# lpf6.net
KiCad netlist of a schematic drawn in Altium Designer
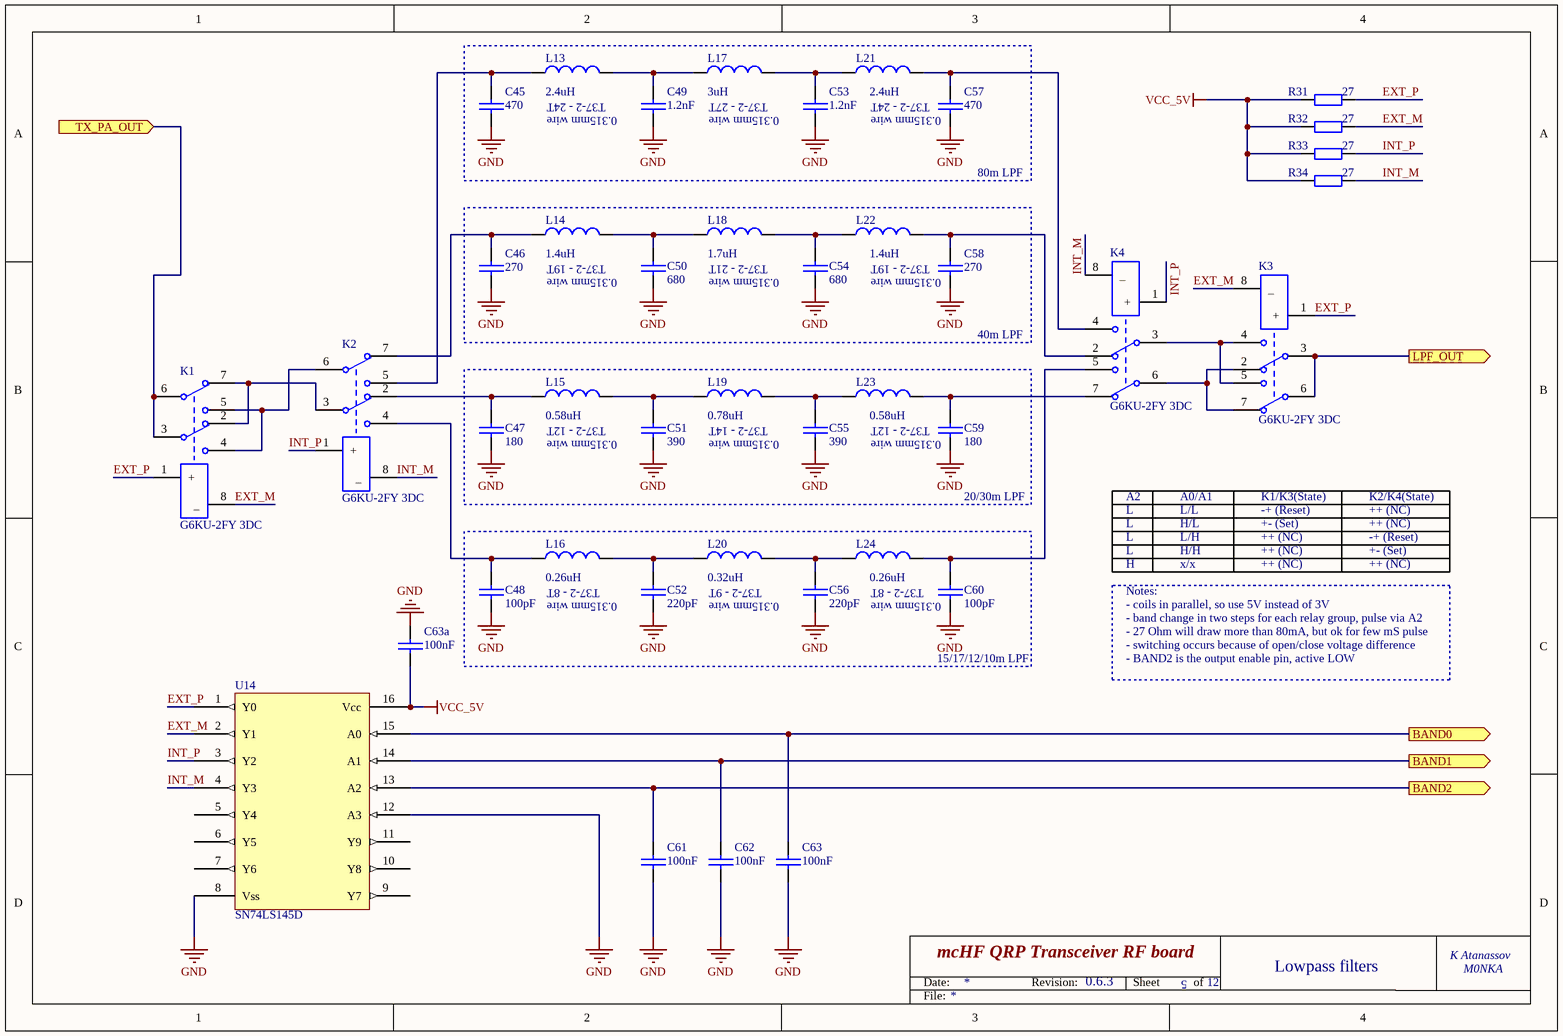
[diagram p0: lpf6.SchDoc]

(export (version "E")
  (design (tool "Eeschema 10.0.6"))
  (components
    (comp (ref "C45")
      (value "470")
      (footprint "0805-Pro")
      (description "Capacitor")
      (libsource (lib "mcHF_rf") (part "CAP"))
    )
    (comp (ref "C46")
      (value "270")
      (footprint "0805-Pro")
      (description "Capacitor")
      (libsource (lib "mcHF_rf") (part "CAP"))
    )
    (comp (ref "C47")
      (value "180")
      (footprint "0805-Pro")
      (description "Capacitor")
      (libsource (lib "mcHF_rf") (part "CAP"))
    )
    (comp (ref "C48")
      (value "100pF")
      (footprint "0805-Pro")
      (description "Capacitor")
      (libsource (lib "mcHF_rf") (part "CAP"))
    )
    (comp (ref "C49")
      (value "1.2nF")
      (footprint "0805-Pro")
      (description "Capacitor")
      (libsource (lib "mcHF_rf") (part "CAP"))
    )
    (comp (ref "C50")
      (value "680")
      (footprint "0805-Pro")
      (description "Capacitor")
      (libsource (lib "mcHF_rf") (part "CAP"))
    )
    (comp (ref "C51")
      (value "390")
      (footprint "0805-Pro")
      (description "Capacitor")
      (libsource (lib "mcHF_rf") (part "CAP"))
    )
    (comp (ref "C52")
      (value "220pF")
      (footprint "0805-Pro")
      (description "Capacitor")
      (libsource (lib "mcHF_rf") (part "CAP"))
    )
    (comp (ref "C53")
      (value "1.2nF")
      (footprint "0805-Pro")
      (description "Capacitor")
      (libsource (lib "mcHF_rf") (part "CAP"))
    )
    (comp (ref "C54")
      (value "680")
      (footprint "0805-Pro")
      (description "Capacitor")
      (libsource (lib "mcHF_rf") (part "CAP"))
    )
    (comp (ref "C55")
      (value "390")
      (footprint "0805-Pro")
      (description "Capacitor")
      (libsource (lib "mcHF_rf") (part "CAP"))
    )
    (comp (ref "C56")
      (value "220pF")
      (footprint "0805-Pro")
      (description "Capacitor")
      (libsource (lib "mcHF_rf") (part "CAP"))
    )
    (comp (ref "C57")
      (value "470")
      (footprint "0805-Pro")
      (description "Capacitor")
      (libsource (lib "mcHF_rf") (part "CAP"))
    )
    (comp (ref "C58")
      (value "270")
      (footprint "0805-Pro")
      (description "Capacitor")
      (libsource (lib "mcHF_rf") (part "CAP"))
    )
    (comp (ref "C59")
      (value "180")
      (footprint "0805-Pro")
      (description "Capacitor")
      (libsource (lib "mcHF_rf") (part "CAP"))
    )
    (comp (ref "C60")
      (value "100pF")
      (footprint "0805-Pro")
      (description "Capacitor")
      (libsource (lib "mcHF_rf") (part "CAP"))
    )
    (comp (ref "C61")
      (value "100nF")
      (footprint "0805-Pro")
      (description "Capacitor")
      (libsource (lib "mcHF_rf") (part "CAP"))
    )
    (comp (ref "C62")
      (value "100nF")
      (footprint "0805-Pro")
      (description "Capacitor")
      (libsource (lib "mcHF_rf") (part "CAP"))
    )
    (comp (ref "C63")
      (value "100nF")
      (footprint "0805-Pro")
      (description "Capacitor")
      (libsource (lib "mcHF_rf") (part "CAP"))
    )
    (comp (ref "C63a")
      (value "100nF")
      (footprint "0805-Pro")
      (description "Capacitor")
      (libsource (lib "mcHF_rf") (part "CAP"))
    )
    (comp (ref "K1")
      (value "G6KU-2FY 3DC")
      (footprint "Omron_2FY")
      (description "Single-winding Latching Relay")
      (libsource (lib "mcHF_rf") (part "G6KU-2FY 3DC"))
    )
    (comp (ref "K2")
      (value "G6KU-2FY 3DC")
      (footprint "Omron_2FY")
      (description "Single-winding Latching Relay")
      (libsource (lib "mcHF_rf") (part "G6KU-2FY 3DC"))
    )
    (comp (ref "K3")
      (value "G6KU-2FY 3DC")
      (footprint "Omron_2FY")
      (description "Single-winding Latching Relay")
      (libsource (lib "mcHF_rf") (part "G6KU-2FY 3DC"))
    )
    (comp (ref "K4")
      (value "G6KU-2FY 3DC")
      (footprint "Omron_2FY")
      (description "Single-winding Latching Relay")
      (libsource (lib "mcHF_rf") (part "G6KU-2FY 3DC"))
    )
    (comp (ref "L13")
      (value "T37-2")
      (footprint "LPF_IND")
      (description "T37-2 handwound inductor")
      (fields (field (name "INDUCTANCE") "2.4uH"))
      (libsource (lib "mcHF_rf") (part "LPF_IND"))
    )
    (comp (ref "L14")
      (value "T37-2")
      (footprint "LPF_IND")
      (description "T37-2 handwound inductor")
      (fields (field (name "INDUCTANCE") "1.4uH"))
      (libsource (lib "mcHF_rf") (part "LPF_IND"))
    )
    (comp (ref "L15")
      (value "T37-2")
      (footprint "LPF_IND")
      (description "T37-2 handwound inductor")
      (fields (field (name "INDUCTANCE") "0.58uH"))
      (libsource (lib "mcHF_rf") (part "LPF_IND"))
    )
    (comp (ref "L16")
      (value "T37-2")
      (footprint "LPF_IND")
      (description "T37-2 handwound inductor")
      (fields (field (name "INDUCTANCE") "0.26uH"))
      (libsource (lib "mcHF_rf") (part "LPF_IND"))
    )
    (comp (ref "L17")
      (value "T37-2")
      (footprint "LPF_IND")
      (description "T37-2 handwound inductor")
      (fields (field (name "INDUCTANCE") "3uH"))
      (libsource (lib "mcHF_rf") (part "LPF_IND"))
    )
    (comp (ref "L18")
      (value "T37-2")
      (footprint "LPF_IND")
      (description "T37-2 handwound inductor")
      (fields (field (name "INDUCTANCE") "1.7uH"))
      (libsource (lib "mcHF_rf") (part "LPF_IND"))
    )
    (comp (ref "L19")
      (value "T37-2")
      (footprint "LPF_IND")
      (description "T37-2 handwound inductor")
      (fields (field (name "INDUCTANCE") "0.78uH"))
      (libsource (lib "mcHF_rf") (part "LPF_IND"))
    )
    (comp (ref "L20")
      (value "T37-2")
      (footprint "LPF_IND")
      (description "T37-2 handwound inductor")
      (fields (field (name "INDUCTANCE") "0.32uH"))
      (libsource (lib "mcHF_rf") (part "LPF_IND"))
    )
    (comp (ref "L21")
      (value "T37-2")
      (footprint "LPF_IND")
      (description "T37-2 handwound inductor")
      (fields (field (name "INDUCTANCE") "2.4uH"))
      (libsource (lib "mcHF_rf") (part "LPF_IND"))
    )
    (comp (ref "L22")
      (value "T37-2")
      (footprint "LPF_IND")
      (description "T37-2 handwound inductor")
      (fields (field (name "INDUCTANCE") "1.4uH"))
      (libsource (lib "mcHF_rf") (part "LPF_IND"))
    )
    (comp (ref "L23")
      (value "T37-2")
      (footprint "LPF_IND")
      (description "T37-2 handwound inductor")
      (fields (field (name "INDUCTANCE") "0.58uH"))
      (libsource (lib "mcHF_rf") (part "LPF_IND"))
    )
    (comp (ref "L24")
      (value "T37-2")
      (footprint "LPF_IND")
      (description "T37-2 handwound inductor")
      (fields (field (name "INDUCTANCE") "0.26uH"))
      (libsource (lib "mcHF_rf") (part "LPF_IND"))
    )
    (comp (ref "R31")
      (value "27")
      (footprint "1206")
      (description "Resistor")
      (libsource (lib "mcHF_rf") (part "RES"))
    )
    (comp (ref "R32")
      (value "27")
      (footprint "1206")
      (description "Resistor")
      (libsource (lib "mcHF_rf") (part "RES"))
    )
    (comp (ref "R33")
      (value "27")
      (footprint "1206")
      (description "Resistor")
      (libsource (lib "mcHF_rf") (part "RES"))
    )
    (comp (ref "R34")
      (value "27")
      (footprint "1206")
      (description "Resistor")
      (libsource (lib "mcHF_rf") (part "RES"))
    )
    (comp (ref "U14")
      (value "SN74LS145D")
      (footprint "SO-16-Pro")
      (description "BCD DECODER/DRIVER")
      (libsource (lib "mcHF_rf") (part "SN74LS145D"))
    )
  )
  (nets
    (net (code "1") (name "/BAND0") (class "Default")
      (node (ref "C63") (pin "2") (pinfunction "2_2") (pintype "passive"))
      (node (ref "U14") (pin "15") (pinfunction "A0_15") (pintype "input"))
    )
    (net (code "2") (name "/BAND1") (class "Default")
      (node (ref "C62") (pin "2") (pinfunction "2_2") (pintype "passive"))
      (node (ref "U14") (pin "14") (pinfunction "A1_14") (pintype "input"))
    )
    (net (code "3") (name "/BAND2") (class "Default")
      (node (ref "C61") (pin "2") (pinfunction "2_2") (pintype "passive"))
      (node (ref "U14") (pin "13") (pinfunction "A2_13") (pintype "input"))
    )
    (net (code "4") (name "/EXT_M") (class "Default")
      (node (ref "K1") (pin "8") (pinfunction "__8") (pintype "passive"))
      (node (ref "K3") (pin "8") (pinfunction "__8") (pintype "passive"))
      (node (ref "R32") (pin "1") (pinfunction "1_1") (pintype "passive"))
      (node (ref "U14") (pin "2") (pinfunction "Y1_2") (pintype "output"))
    )
    (net (code "5") (name "/EXT_P") (class "Default")
      (node (ref "K1") (pin "1") (pinfunction "+_1") (pintype "passive"))
      (node (ref "K3") (pin "1") (pinfunction "+_1") (pintype "passive"))
      (node (ref "R31") (pin "1") (pinfunction "1_1") (pintype "passive"))
      (node (ref "U14") (pin "1") (pinfunction "Y0_1") (pintype "output"))
    )
    (net (code "6") (name "/INT_M") (class "Default")
      (node (ref "K2") (pin "8") (pinfunction "__8") (pintype "passive"))
      (node (ref "K4") (pin "8") (pinfunction "__8") (pintype "passive"))
      (node (ref "R34") (pin "1") (pinfunction "1_1") (pintype "passive"))
      (node (ref "U14") (pin "4") (pinfunction "Y3_4") (pintype "output"))
    )
    (net (code "7") (name "/INT_P") (class "Default")
      (node (ref "K2") (pin "1") (pinfunction "+_1") (pintype "passive"))
      (node (ref "K4") (pin "1") (pinfunction "+_1") (pintype "passive"))
      (node (ref "R33") (pin "1") (pinfunction "1_1") (pintype "passive"))
      (node (ref "U14") (pin "3") (pinfunction "Y2_3") (pintype "output"))
    )
    (net (code "8") (name "/LPF_OUT") (class "Default")
      (node (ref "K3") (pin "3") (pinfunction "3_3") (pintype "passive"))
      (node (ref "K3") (pin "6") (pinfunction "6_6") (pintype "passive"))
    )
    (net (code "9") (name "/TX_PA_OUT") (class "Default")
      (node (ref "K1") (pin "3") (pinfunction "3_3") (pintype "passive"))
      (node (ref "K1") (pin "6") (pinfunction "6_6") (pintype "passive"))
    )
    (net (code "10") (name "GND") (class "Default")
      (node (ref "C45") (pin "2") (pinfunction "2_2") (pintype "passive"))
      (node (ref "C46") (pin "2") (pinfunction "2_2") (pintype "passive"))
      (node (ref "C47") (pin "1") (pinfunction "1_1") (pintype "passive"))
      (node (ref "C48") (pin "1") (pinfunction "1_1") (pintype "passive"))
      (node (ref "C49") (pin "2") (pinfunction "2_2") (pintype "passive"))
      (node (ref "C50") (pin "1") (pinfunction "1_1") (pintype "passive"))
      (node (ref "C51") (pin "1") (pinfunction "1_1") (pintype "passive"))
      (node (ref "C52") (pin "1") (pinfunction "1_1") (pintype "passive"))
      (node (ref "C53") (pin "2") (pinfunction "2_2") (pintype "passive"))
      (node (ref "C54") (pin "1") (pinfunction "1_1") (pintype "passive"))
      (node (ref "C55") (pin "1") (pinfunction "1_1") (pintype "passive"))
      (node (ref "C56") (pin "1") (pinfunction "1_1") (pintype "passive"))
      (node (ref "C57") (pin "2") (pinfunction "2_2") (pintype "passive"))
      (node (ref "C58") (pin "2") (pinfunction "2_2") (pintype "passive"))
      (node (ref "C59") (pin "1") (pinfunction "1_1") (pintype "passive"))
      (node (ref "C60") (pin "1") (pinfunction "1_1") (pintype "passive"))
      (node (ref "C61") (pin "1") (pinfunction "1_1") (pintype "passive"))
      (node (ref "C62") (pin "1") (pinfunction "1_1") (pintype "passive"))
      (node (ref "C63") (pin "1") (pinfunction "1_1") (pintype "passive"))
      (node (ref "C63a") (pin "2") (pinfunction "2_2") (pintype "passive"))
      (node (ref "U14") (pin "12") (pinfunction "A3_12") (pintype "input"))
      (node (ref "U14") (pin "8") (pinfunction "Vss_8") (pintype "power_in"))
    )
    (net (code "11") (name "Net-(C45-Pad1)") (class "Default")
      (node (ref "C45") (pin "1") (pinfunction "1_1") (pintype "passive"))
      (node (ref "K2") (pin "5") (pinfunction "5_5") (pintype "passive"))
      (node (ref "L13") (pin "1") (pinfunction "1_1") (pintype "passive"))
    )
    (net (code "12") (name "Net-(C46-Pad1)") (class "Default")
      (node (ref "C46") (pin "1") (pinfunction "1_1") (pintype "passive"))
      (node (ref "K2") (pin "7") (pinfunction "7_7") (pintype "passive"))
      (node (ref "L14") (pin "1") (pinfunction "1_1") (pintype "passive"))
    )
    (net (code "13") (name "Net-(C47-Pad2)") (class "Default")
      (node (ref "C47") (pin "2") (pinfunction "2_2") (pintype "passive"))
      (node (ref "K2") (pin "2") (pinfunction "2_2") (pintype "passive"))
      (node (ref "L15") (pin "1") (pinfunction "1_1") (pintype "passive"))
    )
    (net (code "14") (name "Net-(C48-Pad2)") (class "Default")
      (node (ref "C48") (pin "2") (pinfunction "2_2") (pintype "passive"))
      (node (ref "K2") (pin "4") (pinfunction "4_4") (pintype "passive"))
      (node (ref "L16") (pin "1") (pinfunction "1_1") (pintype "passive"))
    )
    (net (code "15") (name "Net-(C49-Pad1)") (class "Default")
      (node (ref "C49") (pin "1") (pinfunction "1_1") (pintype "passive"))
      (node (ref "L13") (pin "2") (pinfunction "2_2") (pintype "passive"))
      (node (ref "L17") (pin "1") (pinfunction "1_1") (pintype "passive"))
    )
    (net (code "16") (name "Net-(C50-Pad2)") (class "Default")
      (node (ref "C50") (pin "2") (pinfunction "2_2") (pintype "passive"))
      (node (ref "L14") (pin "2") (pinfunction "2_2") (pintype "passive"))
      (node (ref "L18") (pin "1") (pinfunction "1_1") (pintype "passive"))
    )
    (net (code "17") (name "Net-(C51-Pad2)") (class "Default")
      (node (ref "C51") (pin "2") (pinfunction "2_2") (pintype "passive"))
      (node (ref "L15") (pin "2") (pinfunction "2_2") (pintype "passive"))
      (node (ref "L19") (pin "1") (pinfunction "1_1") (pintype "passive"))
    )
    (net (code "18") (name "Net-(C52-Pad2)") (class "Default")
      (node (ref "C52") (pin "2") (pinfunction "2_2") (pintype "passive"))
      (node (ref "L16") (pin "2") (pinfunction "2_2") (pintype "passive"))
      (node (ref "L20") (pin "1") (pinfunction "1_1") (pintype "passive"))
    )
    (net (code "19") (name "Net-(C53-Pad1)") (class "Default")
      (node (ref "C53") (pin "1") (pinfunction "1_1") (pintype "passive"))
      (node (ref "L17") (pin "2") (pinfunction "2_2") (pintype "passive"))
      (node (ref "L21") (pin "1") (pinfunction "1_1") (pintype "passive"))
    )
    (net (code "20") (name "Net-(C54-Pad2)") (class "Default")
      (node (ref "C54") (pin "2") (pinfunction "2_2") (pintype "passive"))
      (node (ref "L18") (pin "2") (pinfunction "2_2") (pintype "passive"))
      (node (ref "L22") (pin "1") (pinfunction "1_1") (pintype "passive"))
    )
    (net (code "21") (name "Net-(C55-Pad2)") (class "Default")
      (node (ref "C55") (pin "2") (pinfunction "2_2") (pintype "passive"))
      (node (ref "L19") (pin "2") (pinfunction "2_2") (pintype "passive"))
      (node (ref "L23") (pin "1") (pinfunction "1_1") (pintype "passive"))
    )
    (net (code "22") (name "Net-(C56-Pad2)") (class "Default")
      (node (ref "C56") (pin "2") (pinfunction "2_2") (pintype "passive"))
      (node (ref "L20") (pin "2") (pinfunction "2_2") (pintype "passive"))
      (node (ref "L24") (pin "1") (pinfunction "1_1") (pintype "passive"))
    )
    (net (code "23") (name "Net-(C57-Pad1)") (class "Default")
      (node (ref "C57") (pin "1") (pinfunction "1_1") (pintype "passive"))
      (node (ref "K4") (pin "4") (pinfunction "4_4") (pintype "passive"))
      (node (ref "L21") (pin "2") (pinfunction "2_2") (pintype "passive"))
    )
    (net (code "24") (name "Net-(C58-Pad1)") (class "Default")
      (node (ref "C58") (pin "1") (pinfunction "1_1") (pintype "passive"))
      (node (ref "K4") (pin "2") (pinfunction "2_2") (pintype "passive"))
      (node (ref "L22") (pin "2") (pinfunction "2_2") (pintype "passive"))
    )
    (net (code "25") (name "Net-(C59-Pad2)") (class "Default")
      (node (ref "C59") (pin "2") (pinfunction "2_2") (pintype "passive"))
      (node (ref "K4") (pin "7") (pinfunction "7_7") (pintype "passive"))
      (node (ref "L23") (pin "2") (pinfunction "2_2") (pintype "passive"))
    )
    (net (code "26") (name "Net-(C60-Pad2)") (class "Default")
      (node (ref "C60") (pin "2") (pinfunction "2_2") (pintype "passive"))
      (node (ref "K4") (pin "5") (pinfunction "5_5") (pintype "passive"))
      (node (ref "L24") (pin "2") (pinfunction "2_2") (pintype "passive"))
    )
    (net (code "27") (name "Net-(K1-Pad2)") (class "Default")
      (node (ref "K1") (pin "2") (pinfunction "2_2") (pintype "passive"))
      (node (ref "K1") (pin "7") (pinfunction "7_7") (pintype "passive"))
      (node (ref "K2") (pin "3") (pinfunction "3_3") (pintype "passive"))
    )
    (net (code "28") (name "Net-(K1-Pad4)") (class "Default")
      (node (ref "K1") (pin "4") (pinfunction "4_4") (pintype "passive"))
      (node (ref "K1") (pin "5") (pinfunction "5_5") (pintype "passive"))
      (node (ref "K2") (pin "6") (pinfunction "6_6") (pintype "passive"))
    )
    (net (code "29") (name "Net-(K3-Pad2)") (class "Default")
      (node (ref "K3") (pin "2") (pinfunction "2_2") (pintype "passive"))
      (node (ref "K3") (pin "7") (pinfunction "7_7") (pintype "passive"))
      (node (ref "K4") (pin "6") (pinfunction "6_6") (pintype "passive"))
    )
    (net (code "30") (name "Net-(K3-Pad4)") (class "Default")
      (node (ref "K3") (pin "4") (pinfunction "4_4") (pintype "passive"))
      (node (ref "K3") (pin "5") (pinfunction "5_5") (pintype "passive"))
      (node (ref "K4") (pin "3") (pinfunction "3_3") (pintype "passive"))
    )
    (net (code "31") (name "VCC_5V") (class "Default")
      (node (ref "C63a") (pin "1") (pinfunction "1_1") (pintype "passive"))
      (node (ref "R31") (pin "2") (pinfunction "2_2") (pintype "passive"))
      (node (ref "R32") (pin "2") (pinfunction "2_2") (pintype "passive"))
      (node (ref "R33") (pin "2") (pinfunction "2_2") (pintype "passive"))
      (node (ref "R34") (pin "2") (pinfunction "2_2") (pintype "passive"))
      (node (ref "U14") (pin "16") (pinfunction "Vcc_16") (pintype "power_in"))
    )
    (net (code "32") (name "unconnected-(U14-Y4-Pad5)") (class "Default")
      (node (ref "U14") (pin "5") (pinfunction "Y4_5") (pintype "output"))
    )
    (net (code "33") (name "unconnected-(U14-Y5-Pad6)") (class "Default")
      (node (ref "U14") (pin "6") (pinfunction "Y5_6") (pintype "output"))
    )
    (net (code "34") (name "unconnected-(U14-Y6-Pad7)") (class "Default")
      (node (ref "U14") (pin "7") (pinfunction "Y6_7") (pintype "output"))
    )
    (net (code "35") (name "unconnected-(U14-Y7-Pad9)") (class "Default")
      (node (ref "U14") (pin "9") (pinfunction "Y7_9") (pintype "output"))
    )
    (net (code "36") (name "unconnected-(U14-Y8-Pad10)") (class "Default")
      (node (ref "U14") (pin "10") (pinfunction "Y8_10") (pintype "output"))
    )
    (net (code "37") (name "unconnected-(U14-Y9-Pad11)") (class "Default")
      (node (ref "U14") (pin "11") (pinfunction "Y9_11") (pintype "output"))
    )
  )
)
